# Sheet1.net
KiCad netlist of a schematic drawn in Altium Designer
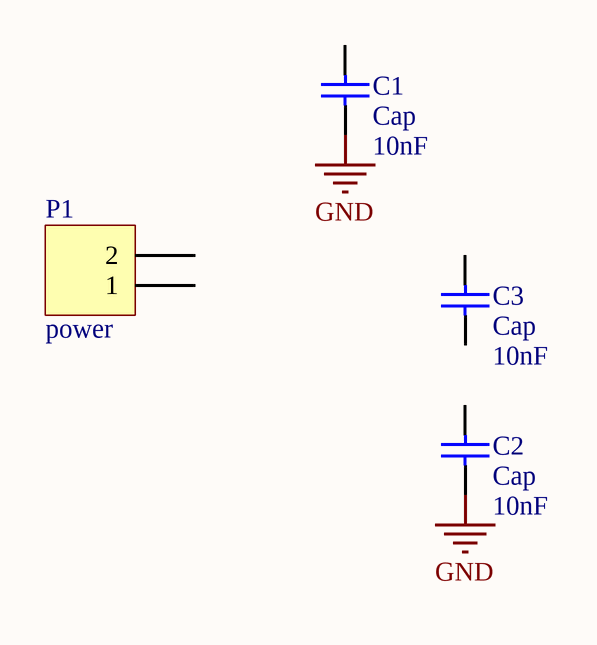
[diagram p0: Sheet1.SchDoc]

(export (version "E")
  (design (tool "Eeschema 10.0.6"))
  (components
    (comp (ref "C1")
      (value "Cap")
      (footprint "RAD-0.3")
      (description "Capacitor")
      (fields (field (name "ALTIUM_VALUE") "10nF") (field (name "PUBLISHER") "Altium Limited"))
      (libsource (lib "Miscellaneous Devices") (part "Cap"))
    )
    (comp (ref "C2")
      (value "Cap")
      (footprint "RAD-0.3")
      (description "Capacitor")
      (fields (field (name "ALTIUM_VALUE") "10nF") (field (name "PUBLISHER") "Altium Limited"))
      (libsource (lib "Miscellaneous Devices") (part "Cap"))
    )
    (comp (ref "C3")
      (value "Cap")
      (footprint "RAD-0.3")
      (description "Capacitor")
      (fields (field (name "ALTIUM_VALUE") "10nF") (field (name "PUBLISHER") "Altium Limited"))
      (libsource (lib "Miscellaneous Devices") (part "Cap"))
    )
    (comp (ref "P1")
      (value "power")
      (footprint "HDR1X2")
      (description "Header, 2-Pin")
      (fields (field (name "PUBLISHER") "Altium Limited"))
      (libsource (lib "Miscellaneous Connectors") (part "Header 2"))
    )
  )
  (nets
    (net (code "1") (name "GND") (class "Default")
      (node (ref "C1") (pin "1") (pinfunction "1_1") (pintype "passive"))
      (node (ref "C2") (pin "1") (pinfunction "1_1") (pintype "passive"))
    )
    (net (code "2") (name "unconnected-(C1-Pad2)") (class "Default")
      (node (ref "C1") (pin "2") (pinfunction "2_2") (pintype "passive"))
    )
    (net (code "3") (name "unconnected-(C2-Pad2)") (class "Default")
      (node (ref "C2") (pin "2") (pinfunction "2_2") (pintype "passive"))
    )
    (net (code "4") (name "unconnected-(C3-Pad1)") (class "Default")
      (node (ref "C3") (pin "1") (pinfunction "1_1") (pintype "passive"))
    )
    (net (code "5") (name "unconnected-(C3-Pad2)") (class "Default")
      (node (ref "C3") (pin "2") (pinfunction "2_2") (pintype "passive"))
    )
    (net (code "6") (name "unconnected-(P1-Pad1)") (class "Default")
      (node (ref "P1") (pin "1") (pinfunction "1_1") (pintype "passive"))
    )
    (net (code "7") (name "unconnected-(P1-Pad2)") (class "Default")
      (node (ref "P1") (pin "2") (pinfunction "2_2") (pintype "passive"))
    )
  )
)
